# Amplifier_ABE_minEv.net
KiCad netlist of a schematic drawn in EAGLE
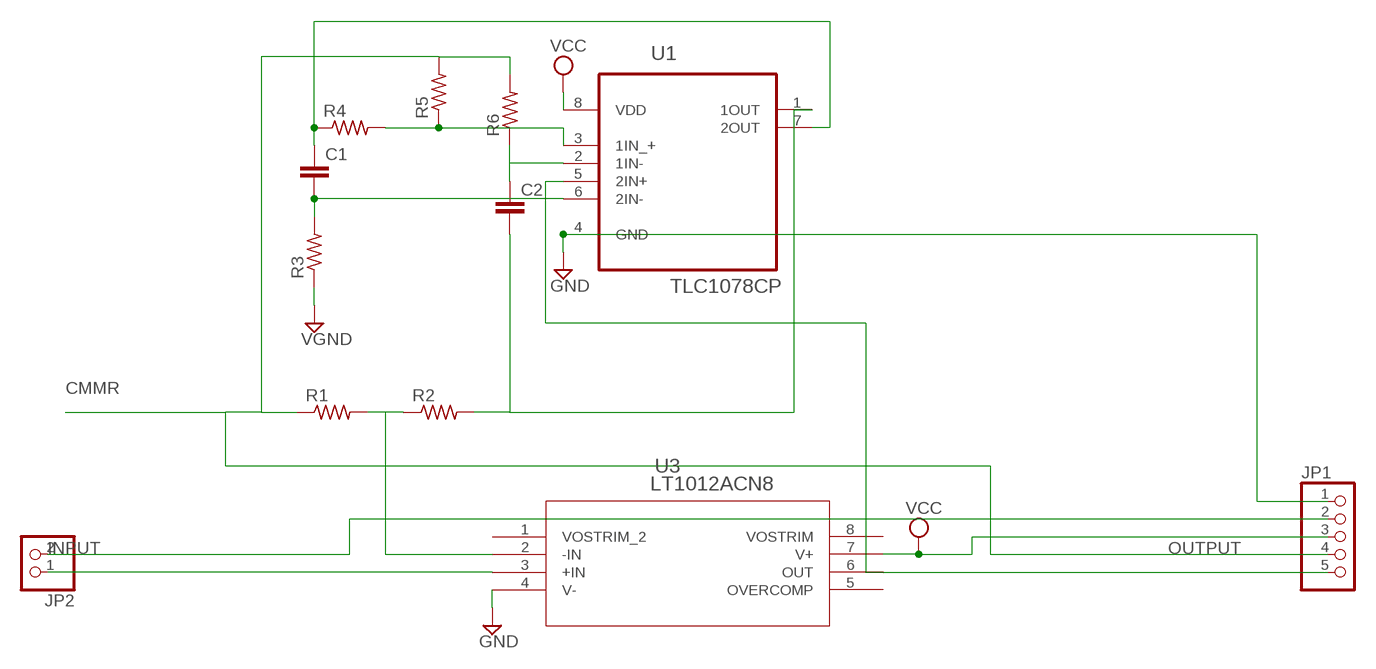
[diagram p0: schematic, sheet 1]

(export (version "E")
  (design (tool "Eeschema 10.0.6"))
  (components
    (comp (ref "C1")
      (value "C-EU025-024X044")
      (footprint "eagle-import:C025-024X044")
      (libsource (lib "eagle-import") (part "C-EU025-024X044"))
    )
    (comp (ref "C2")
      (value "C-EU025-024X044")
      (footprint "eagle-import:C025-024X044")
      (libsource (lib "eagle-import") (part "C-EU025-024X044"))
    )
    (comp (ref "JP1")
      (value "PINHD-1X5")
      (footprint "eagle-import:1X05")
      (libsource (lib "eagle-import") (part "PINHD-1X5"))
    )
    (comp (ref "JP2")
      (value "PINHD-1X2")
      (footprint "eagle-import:1X02")
      (libsource (lib "eagle-import") (part "PINHD-1X2"))
    )
    (comp (ref "R1")
      (value "R-US_0204/7")
      (footprint "eagle-import:0204_7")
      (libsource (lib "eagle-import") (part "R-US_0204/7"))
    )
    (comp (ref "R2")
      (value "R-US_0204/7")
      (footprint "eagle-import:0204_7")
      (libsource (lib "eagle-import") (part "R-US_0204/7"))
    )
    (comp (ref "R3")
      (value "R-US_0204/5")
      (footprint "eagle-import:0204_5")
      (libsource (lib "eagle-import") (part "R-US_0204/5"))
    )
    (comp (ref "R4")
      (value "R-US_0204/7")
      (footprint "eagle-import:0204_7")
      (libsource (lib "eagle-import") (part "R-US_0204/7"))
    )
    (comp (ref "R5")
      (value "R-US_0204/7")
      (footprint "eagle-import:0204_7")
      (libsource (lib "eagle-import") (part "R-US_0204/7"))
    )
    (comp (ref "R6")
      (value "R-US_0204/5")
      (footprint "eagle-import:0204_5")
      (libsource (lib "eagle-import") (part "R-US_0204/5"))
    )
    (comp (ref "U1")
      (value "TLC1078CP")
      (footprint "eagle-import:DIP254P762X508-8")
      (libsource (lib "eagle-import") (part "TLC1078CP"))
    )
    (comp (ref "U3")
      (value "LT1012ACN8")
      (footprint "eagle-import:LT1012ACN8_PDIP-8_N")
      (fields
        (field (name "DIGIKEY_PART_NUMBER") "LT1012ACN8ND")
        (field (name "COPYRIGHT") "Copyright C 2016 Accelerated Designs. All rights reserved")
      )
      (libsource (lib "eagle-import") (part "LT1012ACN8"))
    )
  )
  (nets
    (net (code "1") (name "/CMMR") (class "Default")
      (node (ref "JP1") (pin "4") (pinfunction "4_4") (pintype "passive"))
      (node (ref "R1") (pin "1") (pinfunction "1_1") (pintype "passive"))
      (node (ref "R5") (pin "2") (pinfunction "2_2") (pintype "passive"))
      (node (ref "R6") (pin "2") (pinfunction "2_2") (pintype "passive"))
    )
    (net (code "2") (name "/INPUT") (class "Default")
      (node (ref "JP2") (pin "1") (pinfunction "1_1") (pintype "passive"))
      (node (ref "U3") (pin "3") (pinfunction "+IN_3") (pintype "input"))
    )
    (net (code "3") (name "/OUTPUT") (class "Default")
      (node (ref "JP1") (pin "5") (pinfunction "5_5") (pintype "passive"))
      (node (ref "U1") (pin "5") (pinfunction "2IN+_5") (pintype "input"))
      (node (ref "U3") (pin "6") (pinfunction "OUT_6") (pintype "output"))
    )
    (net (code "4") (name "GND") (class "Default")
      (node (ref "JP1") (pin "1") (pinfunction "1_1") (pintype "passive"))
      (node (ref "R3") (pin "1") (pinfunction "1_1") (pintype "passive"))
      (node (ref "U1") (pin "4") (pinfunction "GND_4") (pintype "passive"))
      (node (ref "U3") (pin "4") (pinfunction "V-_4") (pintype "power_in"))
    )
    (net (code "5") (name "Net-(JP1-Pad2)") (class "Default")
      (node (ref "JP1") (pin "2") (pinfunction "2_2") (pintype "passive"))
      (node (ref "JP2") (pin "2") (pinfunction "2_2") (pintype "passive"))
    )
    (net (code "6") (name "Net-(U1-1IN-)") (class "Default")
      (node (ref "C2") (pin "1") (pinfunction "1_1") (pintype "passive"))
      (node (ref "R6") (pin "1") (pinfunction "1_1") (pintype "passive"))
      (node (ref "U1") (pin "2") (pinfunction "1IN-_2") (pintype "input"))
    )
    (net (code "7") (name "Net-(U1-1IN_+)") (class "Default")
      (node (ref "R4") (pin "2") (pinfunction "2_2") (pintype "passive"))
      (node (ref "R5") (pin "1") (pinfunction "1_1") (pintype "passive"))
      (node (ref "U1") (pin "3") (pinfunction "1IN_+_3") (pintype "input"))
    )
    (net (code "8") (name "Net-(U1-1OUT)") (class "Default")
      (node (ref "C2") (pin "2") (pinfunction "2_2") (pintype "passive"))
      (node (ref "R2") (pin "2") (pinfunction "2_2") (pintype "passive"))
      (node (ref "U1") (pin "1") (pinfunction "1OUT_1") (pintype "output"))
    )
    (net (code "9") (name "Net-(U1-2IN-)") (class "Default")
      (node (ref "C1") (pin "2") (pinfunction "2_2") (pintype "passive"))
      (node (ref "R3") (pin "2") (pinfunction "2_2") (pintype "passive"))
      (node (ref "U1") (pin "6") (pinfunction "2IN-_6") (pintype "input"))
    )
    (net (code "10") (name "Net-(U1-2OUT)") (class "Default")
      (node (ref "C1") (pin "1") (pinfunction "1_1") (pintype "passive"))
      (node (ref "R4") (pin "1") (pinfunction "1_1") (pintype "passive"))
      (node (ref "U1") (pin "7") (pinfunction "2OUT_7") (pintype "output"))
    )
    (net (code "11") (name "Net-(U3--IN)") (class "Default")
      (node (ref "R1") (pin "2") (pinfunction "2_2") (pintype "passive"))
      (node (ref "R2") (pin "1") (pinfunction "1_1") (pintype "passive"))
      (node (ref "U3") (pin "2") (pinfunction "-IN_2") (pintype "input"))
    )
    (net (code "12") (name "VCC") (class "Default")
      (node (ref "JP1") (pin "3") (pinfunction "3_3") (pintype "passive"))
      (node (ref "U1") (pin "8") (pinfunction "VDD_8") (pintype "power_in"))
      (node (ref "U3") (pin "7") (pinfunction "V+_7") (pintype "power_in"))
    )
    (net (code "13") (name "unconnected-(U3-OVERCOMP-Pad5)") (class "Default")
      (node (ref "U3") (pin "5") (pinfunction "OVERCOMP_5") (pintype "passive"))
    )
    (net (code "14") (name "unconnected-(U3-VOSTRIM-Pad8)") (class "Default")
      (node (ref "U3") (pin "8") (pinfunction "VOSTRIM_8") (pintype "passive"))
    )
    (net (code "15") (name "unconnected-(U3-VOSTRIM_2-Pad1)") (class "Default")
      (node (ref "U3") (pin "1") (pinfunction "VOSTRIM_2_1") (pintype "passive"))
    )
  )
)
